# DualGainAmp.net
KiCad netlist of a schematic drawn in EAGLE
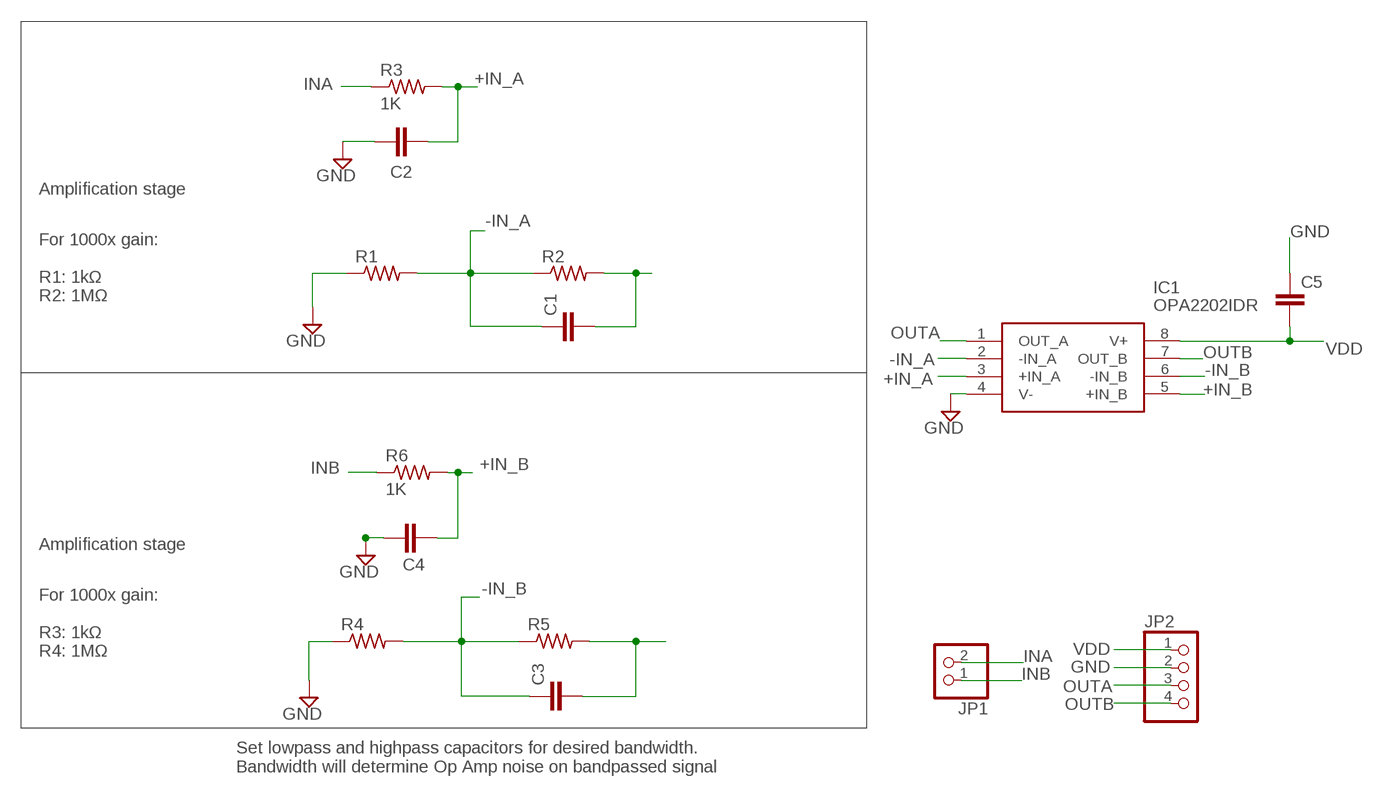
[diagram p0: schematic, sheet 1]

(export (version "E")
  (design (tool "Eeschema 10.0.6"))
  (components
    (comp (ref "C1")
      (value "C-EUC0402")
      (footprint "eagle-import:C0402")
      (libsource (lib "eagle-import") (part "C-EUC0402"))
    )
    (comp (ref "C2")
      (value "C-EUC0402")
      (footprint "eagle-import:C0402")
      (libsource (lib "eagle-import") (part "C-EUC0402"))
    )
    (comp (ref "C3")
      (value "C-EUC0402")
      (footprint "eagle-import:C0402")
      (libsource (lib "eagle-import") (part "C-EUC0402"))
    )
    (comp (ref "C4")
      (value "C-EUC0402")
      (footprint "eagle-import:C0402")
      (libsource (lib "eagle-import") (part "C-EUC0402"))
    )
    (comp (ref "C5")
      (value "C2.5/2")
      (footprint "eagle-import:C2.5-2")
      (libsource (lib "eagle-import") (part "C2.5/2"))
    )
    (comp (ref "IC1")
      (value "OPA2202IDR")
      (footprint "eagle-import:SOIC127P600X175-8N")
      (fields (field (name "MOUSER_PART_NUMBER") "595-OPA2202IDR"))
      (libsource (lib "eagle-import") (part "OPA2202IDR"))
    )
    (comp (ref "JP1")
      (value "PINHD-1X2")
      (footprint "eagle-import:1X02")
      (libsource (lib "eagle-import") (part "PINHD-1X2"))
    )
    (comp (ref "JP2")
      (value "PINHD-1X4")
      (footprint "eagle-import:1X04")
      (libsource (lib "eagle-import") (part "PINHD-1X4"))
    )
    (comp (ref "R1")
      (value "R-US_0204/5")
      (footprint "eagle-import:0204_5")
      (libsource (lib "eagle-import") (part "R-US_0204/5"))
    )
    (comp (ref "R2")
      (value "R-US_0204/5")
      (footprint "eagle-import:0204_5")
      (libsource (lib "eagle-import") (part "R-US_0204/5"))
    )
    (comp (ref "R3")
      (value "1K")
      (footprint "eagle-import:0204_5")
      (libsource (lib "eagle-import") (part "R-US_0204/5"))
    )
    (comp (ref "R4")
      (value "R-US_0204/5")
      (footprint "eagle-import:0204_5")
      (libsource (lib "eagle-import") (part "R-US_0204/5"))
    )
    (comp (ref "R5")
      (value "R-US_0204/5")
      (footprint "eagle-import:0204_5")
      (libsource (lib "eagle-import") (part "R-US_0204/5"))
    )
    (comp (ref "R6")
      (value "1K")
      (footprint "eagle-import:0204_5")
      (libsource (lib "eagle-import") (part "R-US_0204/5"))
    )
  )
  (nets
    (net (code "1") (name "/+IN_A") (class "Default")
      (node (ref "C2") (pin "2") (pinfunction "2_2") (pintype "passive"))
      (node (ref "IC1") (pin "3") (pinfunction "+IN_A_3") (pintype "bidirectional"))
      (node (ref "R3") (pin "2") (pinfunction "2_2") (pintype "passive"))
    )
    (net (code "2") (name "/+IN_B") (class "Default")
      (node (ref "C4") (pin "2") (pinfunction "2_2") (pintype "passive"))
      (node (ref "IC1") (pin "5") (pinfunction "+IN_B_5") (pintype "bidirectional"))
      (node (ref "R6") (pin "2") (pinfunction "2_2") (pintype "passive"))
    )
    (net (code "3") (name "/-IN_A") (class "Default")
      (node (ref "C1") (pin "1") (pinfunction "1_1") (pintype "passive"))
      (node (ref "IC1") (pin "2") (pinfunction "-IN_A_2") (pintype "bidirectional"))
      (node (ref "R1") (pin "2") (pinfunction "2_2") (pintype "passive"))
      (node (ref "R2") (pin "1") (pinfunction "1_1") (pintype "passive"))
    )
    (net (code "4") (name "/-IN_B") (class "Default")
      (node (ref "C3") (pin "1") (pinfunction "1_1") (pintype "passive"))
      (node (ref "IC1") (pin "6") (pinfunction "-IN_B_6") (pintype "bidirectional"))
      (node (ref "R4") (pin "2") (pinfunction "2_2") (pintype "passive"))
      (node (ref "R5") (pin "1") (pinfunction "1_1") (pintype "passive"))
    )
    (net (code "5") (name "/INA") (class "Default")
      (node (ref "JP1") (pin "2") (pinfunction "2_2") (pintype "passive"))
      (node (ref "R3") (pin "1") (pinfunction "1_1") (pintype "passive"))
    )
    (net (code "6") (name "/INB") (class "Default")
      (node (ref "JP1") (pin "1") (pinfunction "1_1") (pintype "passive"))
      (node (ref "R6") (pin "1") (pinfunction "1_1") (pintype "passive"))
    )
    (net (code "7") (name "/OUTA") (class "Default")
      (node (ref "IC1") (pin "1") (pinfunction "OUT_A_1") (pintype "bidirectional"))
      (node (ref "JP2") (pin "3") (pinfunction "3_3") (pintype "passive"))
    )
    (net (code "8") (name "/OUTB") (class "Default")
      (node (ref "IC1") (pin "7") (pinfunction "OUT_B_7") (pintype "bidirectional"))
      (node (ref "JP2") (pin "4") (pinfunction "4_4") (pintype "passive"))
    )
    (net (code "9") (name "/VDD") (class "Default")
      (node (ref "C5") (pin "2") (pinfunction "2_2") (pintype "passive"))
      (node (ref "IC1") (pin "8") (pinfunction "V+_8") (pintype "bidirectional"))
      (node (ref "JP2") (pin "1") (pinfunction "1_1") (pintype "passive"))
    )
    (net (code "10") (name "GND") (class "Default")
      (node (ref "C2") (pin "1") (pinfunction "1_1") (pintype "passive"))
      (node (ref "C4") (pin "1") (pinfunction "1_1") (pintype "passive"))
      (node (ref "C5") (pin "1") (pinfunction "1_1") (pintype "passive"))
      (node (ref "IC1") (pin "4") (pinfunction "V-_4") (pintype "bidirectional"))
      (node (ref "JP2") (pin "2") (pinfunction "2_2") (pintype "passive"))
      (node (ref "R1") (pin "1") (pinfunction "1_1") (pintype "passive"))
      (node (ref "R4") (pin "1") (pinfunction "1_1") (pintype "passive"))
    )
    (net (code "11") (name "Net-(C1-Pad2)") (class "Default")
      (node (ref "C1") (pin "2") (pinfunction "2_2") (pintype "passive"))
      (node (ref "R2") (pin "2") (pinfunction "2_2") (pintype "passive"))
    )
    (net (code "12") (name "Net-(C3-Pad2)") (class "Default")
      (node (ref "C3") (pin "2") (pinfunction "2_2") (pintype "passive"))
      (node (ref "R5") (pin "2") (pinfunction "2_2") (pintype "passive"))
    )
  )
)
